# LB_BIT_o21_number-v03_rev5_4.net
KiCad netlist of a schematic drawn in EAGLE
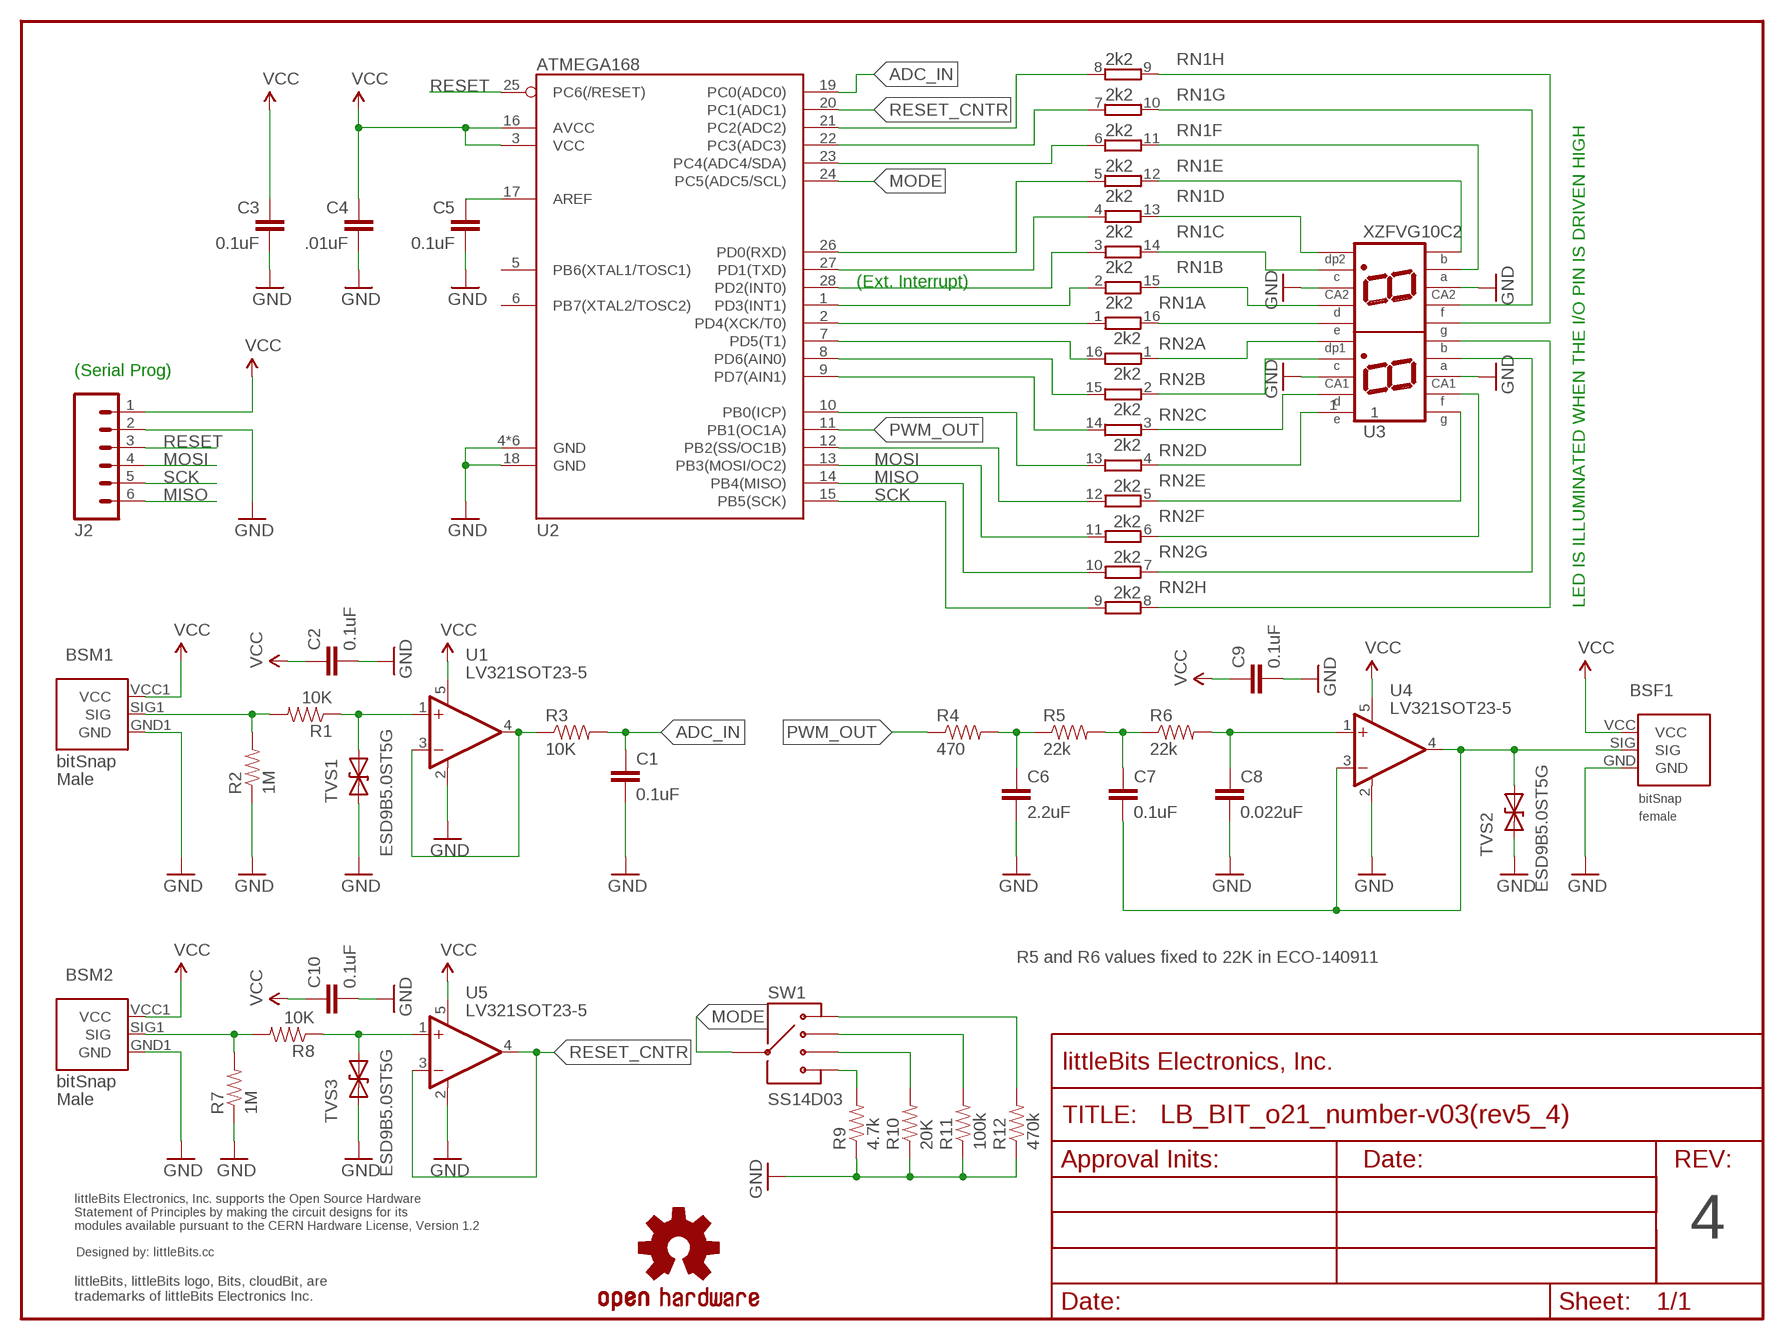
[diagram p0: schematic, sheet 1]

(export (version "E")
  (design (tool "Eeschema 10.0.6"))
  (components
    (comp (ref "BSF1")
      (value "BITSNAP_V03_FEMALE")
      (footprint "eagle-import:BITSNAP_V03_FEMALE")
      (libsource (lib "eagle-import") (part "BITSNAP_V03_FEMALE"))
    )
    (comp (ref "BSM1")
      (value "BITSNAP_V03_MALE")
      (footprint "eagle-import:BITSNAP_V03_MALE")
      (libsource (lib "eagle-import") (part "BITSNAP_V03_MALE"))
    )
    (comp (ref "BSM2")
      (value "BITSNAP_V03_MALE")
      (footprint "eagle-import:BITSNAP_V03_MALE")
      (libsource (lib "eagle-import") (part "BITSNAP_V03_MALE"))
    )
    (comp (ref "C1")
      (value "0.1uF")
      (footprint "eagle-import:CAP-0603")
      (libsource (lib "eagle-import") (part "CAPCAP-0603"))
    )
    (comp (ref "C2")
      (value "0.1uF")
      (footprint "eagle-import:CAP-0603")
      (libsource (lib "eagle-import") (part "CAPCAP-0603"))
    )
    (comp (ref "C3")
      (value "0.1uF")
      (footprint "eagle-import:CAP-0603")
      (libsource (lib "eagle-import") (part "CAPCAP-0603"))
    )
    (comp (ref "C4")
      (value ".01uF")
      (footprint "eagle-import:CAP-0603")
      (libsource (lib "eagle-import") (part "CAPCAP-0603"))
    )
    (comp (ref "C5")
      (value "0.1uF")
      (footprint "eagle-import:CAP-0603")
      (libsource (lib "eagle-import") (part "CAPCAP-0603"))
    )
    (comp (ref "C6")
      (value "2.2uF")
      (footprint "eagle-import:CAP-0603")
      (libsource (lib "eagle-import") (part "CAPCAP-0603"))
    )
    (comp (ref "C7")
      (value "0.1uF")
      (footprint "eagle-import:CAP-0603")
      (libsource (lib "eagle-import") (part "CAPCAP-0603"))
    )
    (comp (ref "C8")
      (value "0.022uF")
      (footprint "eagle-import:CAP-0603")
      (libsource (lib "eagle-import") (part "CAPCAP-0603"))
    )
    (comp (ref "C9")
      (value "0.1uF")
      (footprint "eagle-import:CAP-0603")
      (libsource (lib "eagle-import") (part "CAPCAP-0603"))
    )
    (comp (ref "C10")
      (value "0.1uF")
      (footprint "eagle-import:CAP-0603")
      (libsource (lib "eagle-import") (part "CAPCAP-0603"))
    )
    (comp (ref "J2")
      (value "HRD-60.1INCH_NO_SILKSCREEN")
      (footprint "eagle-import:SIP6-SM-0.1IN-NOS.S.")
      (libsource (lib "eagle-import") (part "HRD-60.1INCH_NO_SILKSCREEN"))
    )
    (comp (ref "R1")
      (value "10K")
      (footprint "eagle-import:RES-0603")
      (libsource (lib "eagle-import") (part "RESISTOR0603"))
    )
    (comp (ref "R2")
      (value "1M")
      (footprint "eagle-import:RES-0603")
      (libsource (lib "eagle-import") (part "RESISTOR0603"))
    )
    (comp (ref "R3")
      (value "10K")
      (footprint "eagle-import:RES-0603")
      (libsource (lib "eagle-import") (part "RESISTOR0603"))
    )
    (comp (ref "R4")
      (value "470")
      (footprint "eagle-import:RES-0603")
      (libsource (lib "eagle-import") (part "RESISTOR0603"))
    )
    (comp (ref "R5")
      (value "22k")
      (footprint "eagle-import:RES-0603")
      (libsource (lib "eagle-import") (part "RESISTOR0603"))
    )
    (comp (ref "R6")
      (value "22k")
      (footprint "eagle-import:RES-0603")
      (libsource (lib "eagle-import") (part "RESISTOR0603"))
    )
    (comp (ref "R7")
      (value "1M")
      (footprint "eagle-import:RES-0603")
      (libsource (lib "eagle-import") (part "RESISTOR0603"))
    )
    (comp (ref "R8")
      (value "10K")
      (footprint "eagle-import:RES-0603")
      (libsource (lib "eagle-import") (part "RESISTOR0603"))
    )
    (comp (ref "R9")
      (value "4.7k")
      (footprint "eagle-import:RES-0603")
      (libsource (lib "eagle-import") (part "RESISTOR0603"))
    )
    (comp (ref "R10")
      (value "20K")
      (footprint "eagle-import:RES-0603")
      (libsource (lib "eagle-import") (part "RESISTOR0603"))
    )
    (comp (ref "R11")
      (value "100k")
      (footprint "eagle-import:RES-0603")
      (libsource (lib "eagle-import") (part "RESISTOR0603"))
    )
    (comp (ref "R12")
      (value "470k")
      (footprint "eagle-import:RES-0603")
      (libsource (lib "eagle-import") (part "RESISTOR0603"))
    )
    (comp (ref "RN1")
      (value "2k2")
      (footprint "eagle-import:EXB2HV")
      (libsource (lib "eagle-import") (part "RES_ARRAY8_DIPEXB2HV"))
    )
    (comp (ref "RN2")
      (value "2k2")
      (footprint "eagle-import:EXB2HV")
      (libsource (lib "eagle-import") (part "RES_ARRAY8_DIPEXB2HV"))
    )
    (comp (ref "SW1")
      (value "SS14D03")
      (footprint "eagle-import:SWITCH-SLIDE-SP4T-SS14D03")
      (fields (field (name "MFG") "Vimex") (field (name "MPN") "SS-14D03"))
      (libsource (lib "eagle-import") (part "SWITCH-SLIDE-SS14D03"))
    )
    (comp (ref "TVS1")
      (value "ESD9B5.0ST5G")
      (footprint "eagle-import:SOD-923")
      (libsource (lib "eagle-import") (part "DIODE-TVSSOD-923"))
    )
    (comp (ref "TVS2")
      (value "ESD9B5.0ST5G")
      (footprint "eagle-import:SOD-923")
      (libsource (lib "eagle-import") (part "DIODE-TVSSOD-923"))
    )
    (comp (ref "TVS3")
      (value "ESD9B5.0ST5G")
      (footprint "eagle-import:SOD-923")
      (libsource (lib "eagle-import") (part "DIODE-TVSSOD-923"))
    )
    (comp (ref "U$1")
      (value "FRAME-LETTER-OHWOHW")
      (footprint "eagle-import:FABDWG01-OHW")
      (libsource (lib "eagle-import") (part "FRAME-LETTER-OHWOHW"))
    )
    (comp (ref "U$2")
      (value "OSHWCREDIT")
      (footprint "eagle-import:OSHWCREDIT")
      (libsource (lib "eagle-import") (part "OSHWCREDIT"))
    )
    (comp (ref "U$27")
      (value "OSHW-LOGOL")
      (footprint "eagle-import:OSHW-LOGO-L")
      (libsource (lib "eagle-import") (part "OSHW-LOGOL"))
    )
    (comp (ref "U1")
      (value "LV321SOT23-5")
      (footprint "eagle-import:SOT23-5")
      (libsource (lib "eagle-import") (part "LV321SOT23-5"))
    )
    (comp (ref "U2")
      (value "ATMEGA168")
      (footprint "eagle-import:VQFN28")
      (libsource (lib "eagle-import") (part "ATMEGA168-28PINVFQFN-28"))
    )
    (comp (ref "U3")
      (value "XZFVG10C2")
      (footprint "eagle-import:LED-DUAL7SEG-SM")
      (libsource (lib "eagle-import") (part "LED-DUAL7SEG10.16MMDIGITS"))
    )
    (comp (ref "U4")
      (value "LV321SOT23-5")
      (footprint "eagle-import:SOT23-5")
      (libsource (lib "eagle-import") (part "LV321SOT23-5"))
    )
    (comp (ref "U5")
      (value "LV321SOT23-5")
      (footprint "eagle-import:SOT23-5")
      (libsource (lib "eagle-import") (part "LV321SOT23-5"))
    )
  )
  (nets
    (net (code "1") (name "/MISO") (class "Default")
      (node (ref "J2") (pin "6") (pinfunction "6_6") (pintype "passive"))
      (node (ref "RN2") (pin "10") (pinfunction "2_10") (pintype "passive"))
      (node (ref "U2") (pin "14") (pinfunction "PB4(MISO)_14") (pintype "bidirectional"))
    )
    (net (code "2") (name "/MOSI") (class "Default")
      (node (ref "J2") (pin "4") (pinfunction "4_4") (pintype "passive"))
      (node (ref "RN2") (pin "11") (pinfunction "2_11") (pintype "passive"))
      (node (ref "U2") (pin "13") (pinfunction "PB3(MOSI/OC2)_13") (pintype "bidirectional"))
    )
    (net (code "3") (name "/RESET") (class "Default")
      (node (ref "J2") (pin "3") (pinfunction "3_3") (pintype "passive"))
      (node (ref "U2") (pin "25") (pinfunction "PC6(/RESET)_25") (pintype "bidirectional"))
    )
    (net (code "4") (name "/SCK") (class "Default")
      (node (ref "J2") (pin "5") (pinfunction "5_5") (pintype "passive"))
      (node (ref "RN2") (pin "9") (pinfunction "2_9") (pintype "passive"))
      (node (ref "U2") (pin "15") (pinfunction "PB5(SCK)_15") (pintype "bidirectional"))
    )
    (net (code "5") (name "ADC_IN") (class "Default")
      (node (ref "C1") (pin "1") (pinfunction "1_1") (pintype "passive"))
      (node (ref "R3") (pin "2") (pinfunction "2_2") (pintype "passive"))
      (node (ref "U2") (pin "19") (pinfunction "PC0(ADC0)_19") (pintype "bidirectional"))
    )
    (net (code "6") (name "GND") (class "Default")
      (node (ref "BSF1") (pin "GND") (pinfunction "GND_GND") (pintype "bidirectional"))
      (node (ref "BSM1") (pin "GND1") (pinfunction "GND_GND1") (pintype "bidirectional"))
      (node (ref "BSM2") (pin "GND1") (pinfunction "GND_GND1") (pintype "bidirectional"))
      (node (ref "C1") (pin "2") (pinfunction "2_2") (pintype "passive"))
      (node (ref "C10") (pin "2") (pinfunction "2_2") (pintype "passive"))
      (node (ref "C2") (pin "2") (pinfunction "2_2") (pintype "passive"))
      (node (ref "C3") (pin "2") (pinfunction "2_2") (pintype "passive"))
      (node (ref "C4") (pin "2") (pinfunction "2_2") (pintype "passive"))
      (node (ref "C5") (pin "2") (pinfunction "2_2") (pintype "passive"))
      (node (ref "C6") (pin "2") (pinfunction "2_2") (pintype "passive"))
      (node (ref "C8") (pin "2") (pinfunction "2_2") (pintype "passive"))
      (node (ref "C9") (pin "2") (pinfunction "2_2") (pintype "passive"))
      (node (ref "J2") (pin "2") (pinfunction "2_2") (pintype "passive"))
      (node (ref "R10") (pin "1") (pinfunction "1_1") (pintype "passive"))
      (node (ref "R11") (pin "1") (pinfunction "1_1") (pintype "passive"))
      (node (ref "R12") (pin "1") (pinfunction "1_1") (pintype "passive"))
      (node (ref "R2") (pin "1") (pinfunction "1_1") (pintype "passive"))
      (node (ref "R7") (pin "1") (pinfunction "1_1") (pintype "passive"))
      (node (ref "R9") (pin "1") (pinfunction "1_1") (pintype "passive"))
      (node (ref "TVS1") (pin "1") (pinfunction "A_1") (pintype "passive"))
      (node (ref "TVS2") (pin "1") (pinfunction "A_1") (pintype "passive"))
      (node (ref "TVS3") (pin "1") (pinfunction "A_1") (pintype "passive"))
      (node (ref "U1") (pin "2") (pinfunction "V-_2") (pintype "power_in"))
      (node (ref "U2") (pin "18") (pinfunction "GND_18") (pintype "bidirectional"))
      (node (ref "U2") (pin "4") (pinfunction "GND_4") (pintype "bidirectional"))
      (node (ref "U2") (pin "TH") (pinfunction "GND_TH") (pintype "bidirectional"))
      (node (ref "U2") (pin "TH@1") (pinfunction "GND_TH@1") (pintype "bidirectional"))
      (node (ref "U2") (pin "TH@2") (pinfunction "GND_TH@2") (pintype "bidirectional"))
      (node (ref "U2") (pin "TH@3") (pinfunction "GND_TH@3") (pintype "bidirectional"))
      (node (ref "U2") (pin "TH@4") (pinfunction "GND_TH@4") (pintype "bidirectional"))
      (node (ref "U3") (pin "13") (pinfunction "13_13") (pintype "passive"))
      (node (ref "U3") (pin "18") (pinfunction "18_18") (pintype "passive"))
      (node (ref "U3") (pin "3") (pinfunction "3_3") (pintype "passive"))
      (node (ref "U3") (pin "8") (pinfunction "8_8") (pintype "passive"))
      (node (ref "U4") (pin "2") (pinfunction "V-_2") (pintype "power_in"))
      (node (ref "U5") (pin "2") (pinfunction "V-_2") (pintype "power_in"))
    )
    (net (code "7") (name "MODE") (class "Default")
      (node (ref "SW1") (pin "COM") (pinfunction "COM_COM") (pintype "bidirectional"))
      (node (ref "U2") (pin "24") (pinfunction "PC5(ADC5/SCL)_24") (pintype "bidirectional"))
    )
    (net (code "8") (name "Net-(BSM1-SIG)") (class "Default")
      (node (ref "BSM1") (pin "SIG1") (pinfunction "SIG_SIG1") (pintype "bidirectional"))
      (node (ref "R1") (pin "2") (pinfunction "2_2") (pintype "passive"))
      (node (ref "R2") (pin "2") (pinfunction "2_2") (pintype "passive"))
    )
    (net (code "9") (name "Net-(BSM2-SIG)") (class "Default")
      (node (ref "BSM2") (pin "SIG1") (pinfunction "SIG_SIG1") (pintype "bidirectional"))
      (node (ref "R7") (pin "2") (pinfunction "2_2") (pintype "passive"))
      (node (ref "R8") (pin "2") (pinfunction "2_2") (pintype "passive"))
    )
    (net (code "10") (name "Net-(C6-Pad1)") (class "Default")
      (node (ref "C6") (pin "1") (pinfunction "1_1") (pintype "passive"))
      (node (ref "R4") (pin "2") (pinfunction "2_2") (pintype "passive"))
      (node (ref "R5") (pin "1") (pinfunction "1_1") (pintype "passive"))
    )
    (net (code "11") (name "Net-(C7-Pad1)") (class "Default")
      (node (ref "C7") (pin "1") (pinfunction "1_1") (pintype "passive"))
      (node (ref "R5") (pin "2") (pinfunction "2_2") (pintype "passive"))
      (node (ref "R6") (pin "1") (pinfunction "1_1") (pintype "passive"))
    )
    (net (code "12") (name "Net-(R9-Pad2)") (class "Default")
      (node (ref "R9") (pin "2") (pinfunction "2_2") (pintype "passive"))
      (node (ref "SW1") (pin "4") (pinfunction "4_4") (pintype "bidirectional"))
    )
    (net (code "13") (name "Net-(R10-Pad2)") (class "Default")
      (node (ref "R10") (pin "2") (pinfunction "2_2") (pintype "passive"))
      (node (ref "SW1") (pin "3") (pinfunction "3_3") (pintype "bidirectional"))
    )
    (net (code "14") (name "Net-(R11-Pad2)") (class "Default")
      (node (ref "R11") (pin "2") (pinfunction "2_2") (pintype "passive"))
      (node (ref "SW1") (pin "2") (pinfunction "2_2") (pintype "bidirectional"))
    )
    (net (code "15") (name "Net-(R12-Pad2)") (class "Default")
      (node (ref "R12") (pin "2") (pinfunction "2_2") (pintype "passive"))
      (node (ref "SW1") (pin "1") (pinfunction "1_1") (pintype "bidirectional"))
    )
    (net (code "16") (name "Net-(RN1A-2)") (class "Default")
      (node (ref "RN1") (pin "16") (pinfunction "2_16") (pintype "passive"))
      (node (ref "U3") (pin "6") (pinfunction "6_6") (pintype "passive"))
    )
    (net (code "17") (name "Net-(RN1B-1)") (class "Default")
      (node (ref "RN1") (pin "2") (pinfunction "1_2") (pintype "passive"))
      (node (ref "U2") (pin "1") (pinfunction "PD3(INT1)_1") (pintype "bidirectional"))
    )
    (net (code "18") (name "Net-(RN1B-2)") (class "Default")
      (node (ref "RN1") (pin "15") (pinfunction "2_15") (pintype "passive"))
      (node (ref "U3") (pin "7") (pinfunction "7_7") (pintype "passive"))
    )
    (net (code "19") (name "Net-(RN1C-1)") (class "Default")
      (node (ref "RN1") (pin "3") (pinfunction "1_3") (pintype "passive"))
      (node (ref "U2") (pin "28") (pinfunction "PD2(INT0)_28") (pintype "bidirectional"))
    )
    (net (code "20") (name "Net-(RN1C-2)") (class "Default")
      (node (ref "RN1") (pin "14") (pinfunction "2_14") (pintype "passive"))
      (node (ref "U3") (pin "9") (pinfunction "9_9") (pintype "passive"))
    )
    (net (code "21") (name "Net-(RN1D-1)") (class "Default")
      (node (ref "RN1") (pin "4") (pinfunction "1_4") (pintype "passive"))
      (node (ref "U2") (pin "27") (pinfunction "PD1(TXD)_27") (pintype "bidirectional"))
    )
    (net (code "22") (name "Net-(RN1D-2)") (class "Default")
      (node (ref "RN1") (pin "13") (pinfunction "2_13") (pintype "passive"))
      (node (ref "U3") (pin "10") (pinfunction "10_10") (pintype "passive"))
    )
    (net (code "23") (name "Net-(RN1E-1)") (class "Default")
      (node (ref "RN1") (pin "5") (pinfunction "1_5") (pintype "passive"))
      (node (ref "U2") (pin "26") (pinfunction "PD0(RXD)_26") (pintype "bidirectional"))
    )
    (net (code "24") (name "Net-(RN1E-2)") (class "Default")
      (node (ref "RN1") (pin "12") (pinfunction "2_12") (pintype "passive"))
      (node (ref "U3") (pin "11") (pinfunction "11_11") (pintype "passive"))
    )
    (net (code "25") (name "Net-(RN1F-1)") (class "Default")
      (node (ref "RN1") (pin "6") (pinfunction "1_6") (pintype "passive"))
      (node (ref "U2") (pin "23") (pinfunction "PC4(ADC4/SDA)_23") (pintype "bidirectional"))
    )
    (net (code "26") (name "Net-(RN1F-2)") (class "Default")
      (node (ref "RN1") (pin "11") (pinfunction "2_11") (pintype "passive"))
      (node (ref "U3") (pin "12") (pinfunction "12_12") (pintype "passive"))
    )
    (net (code "27") (name "Net-(RN1G-1)") (class "Default")
      (node (ref "RN1") (pin "7") (pinfunction "1_7") (pintype "passive"))
      (node (ref "U2") (pin "22") (pinfunction "PC3(ADC3)_22") (pintype "bidirectional"))
    )
    (net (code "28") (name "Net-(RN1G-2)") (class "Default")
      (node (ref "RN1") (pin "10") (pinfunction "2_10") (pintype "passive"))
      (node (ref "U3") (pin "14") (pinfunction "14_14") (pintype "passive"))
    )
    (net (code "29") (name "Net-(RN1H-1)") (class "Default")
      (node (ref "RN1") (pin "8") (pinfunction "1_8") (pintype "passive"))
      (node (ref "U2") (pin "21") (pinfunction "PC2(ADC2)_21") (pintype "bidirectional"))
    )
    (net (code "30") (name "Net-(RN1H-2)") (class "Default")
      (node (ref "RN1") (pin "9") (pinfunction "2_9") (pintype "passive"))
      (node (ref "U3") (pin "15") (pinfunction "15_15") (pintype "passive"))
    )
    (net (code "31") (name "Net-(RN2-Pad1)") (class "Default")
      (node (ref "RN2") (pin "1") (pinfunction "1_1") (pintype "passive"))
      (node (ref "U3") (pin "5") (pinfunction "5_5") (pintype "passive"))
    )
    (net (code "32") (name "Net-(RN2A-2)") (class "Default")
      (node (ref "RN2") (pin "16") (pinfunction "2_16") (pintype "passive"))
      (node (ref "U2") (pin "7") (pinfunction "PD5(T1)_7") (pintype "bidirectional"))
    )
    (net (code "33") (name "Net-(RN2B-1)") (class "Default")
      (node (ref "RN2") (pin "2") (pinfunction "1_2") (pintype "passive"))
      (node (ref "U3") (pin "4") (pinfunction "4_4") (pintype "passive"))
    )
    (net (code "34") (name "Net-(RN2B-2)") (class "Default")
      (node (ref "RN2") (pin "15") (pinfunction "2_15") (pintype "passive"))
      (node (ref "U2") (pin "8") (pinfunction "PD6(AIN0)_8") (pintype "bidirectional"))
    )
    (net (code "35") (name "Net-(RN2C-1)") (class "Default")
      (node (ref "RN2") (pin "3") (pinfunction "1_3") (pintype "passive"))
      (node (ref "U3") (pin "2") (pinfunction "2_2") (pintype "passive"))
    )
    (net (code "36") (name "Net-(RN2C-2)") (class "Default")
      (node (ref "RN2") (pin "14") (pinfunction "2_14") (pintype "passive"))
      (node (ref "U2") (pin "9") (pinfunction "PD7(AIN1)_9") (pintype "bidirectional"))
    )
    (net (code "37") (name "Net-(RN2D-1)") (class "Default")
      (node (ref "RN2") (pin "4") (pinfunction "1_4") (pintype "passive"))
      (node (ref "U3") (pin "1") (pinfunction "1_1") (pintype "passive"))
    )
    (net (code "38") (name "Net-(RN2D-2)") (class "Default")
      (node (ref "RN2") (pin "13") (pinfunction "2_13") (pintype "passive"))
      (node (ref "U2") (pin "10") (pinfunction "PB0(ICP)_10") (pintype "bidirectional"))
    )
    (net (code "39") (name "Net-(RN2E-1)") (class "Default")
      (node (ref "RN2") (pin "5") (pinfunction "1_5") (pintype "passive"))
      (node (ref "U3") (pin "20") (pinfunction "20_20") (pintype "passive"))
    )
    (net (code "40") (name "Net-(RN2E-2)") (class "Default")
      (node (ref "RN2") (pin "12") (pinfunction "2_12") (pintype "passive"))
      (node (ref "U2") (pin "12") (pinfunction "PB2(SS/OC1B)_12") (pintype "bidirectional"))
    )
    (net (code "41") (name "Net-(RN2F-1)") (class "Default")
      (node (ref "RN2") (pin "6") (pinfunction "1_6") (pintype "passive"))
      (node (ref "U3") (pin "19") (pinfunction "19_19") (pintype "passive"))
    )
    (net (code "42") (name "Net-(RN2G-1)") (class "Default")
      (node (ref "RN2") (pin "7") (pinfunction "1_7") (pintype "passive"))
      (node (ref "U3") (pin "17") (pinfunction "17_17") (pintype "passive"))
    )
    (net (code "43") (name "Net-(RN2H-1)") (class "Default")
      (node (ref "RN2") (pin "8") (pinfunction "1_8") (pintype "passive"))
      (node (ref "U3") (pin "16") (pinfunction "16_16") (pintype "passive"))
    )
    (net (code "44") (name "Net-(TVS1-C)") (class "Default")
      (node (ref "R1") (pin "1") (pinfunction "1_1") (pintype "passive"))
      (node (ref "TVS1") (pin "2") (pinfunction "C_2") (pintype "passive"))
      (node (ref "U1") (pin "1") (pinfunction "+IN_1") (pintype "input"))
    )
    (net (code "45") (name "Net-(TVS2-C)") (class "Default")
      (node (ref "BSF1") (pin "SIG") (pinfunction "SIG_SIG") (pintype "bidirectional"))
      (node (ref "C7") (pin "2") (pinfunction "2_2") (pintype "passive"))
      (node (ref "TVS2") (pin "2") (pinfunction "C_2") (pintype "passive"))
      (node (ref "U4") (pin "3") (pinfunction "-IN_3") (pintype "input"))
      (node (ref "U4") (pin "4") (pinfunction "OUT_4") (pintype "output"))
    )
    (net (code "46") (name "Net-(TVS3-C)") (class "Default")
      (node (ref "R8") (pin "1") (pinfunction "1_1") (pintype "passive"))
      (node (ref "TVS3") (pin "2") (pinfunction "C_2") (pintype "passive"))
      (node (ref "U5") (pin "1") (pinfunction "+IN_1") (pintype "input"))
    )
    (net (code "47") (name "Net-(U1--IN)") (class "Default")
      (node (ref "R3") (pin "1") (pinfunction "1_1") (pintype "passive"))
      (node (ref "U1") (pin "3") (pinfunction "-IN_3") (pintype "input"))
      (node (ref "U1") (pin "4") (pinfunction "OUT_4") (pintype "output"))
    )
    (net (code "48") (name "Net-(U2-AREF)") (class "Default")
      (node (ref "C5") (pin "1") (pinfunction "1_1") (pintype "passive"))
      (node (ref "U2") (pin "17") (pinfunction "AREF_17") (pintype "bidirectional"))
    )
    (net (code "49") (name "Net-(U2-PD4(XCK{slash}T0))") (class "Default")
      (node (ref "RN1") (pin "1") (pinfunction "1_1") (pintype "passive"))
      (node (ref "U2") (pin "2") (pinfunction "PD4(XCK/T0)_2") (pintype "bidirectional"))
    )
    (net (code "50") (name "Net-(U4-+IN)") (class "Default")
      (node (ref "C8") (pin "1") (pinfunction "1_1") (pintype "passive"))
      (node (ref "R6") (pin "2") (pinfunction "2_2") (pintype "passive"))
      (node (ref "U4") (pin "1") (pinfunction "+IN_1") (pintype "input"))
    )
    (net (code "51") (name "PWM_OUT") (class "Default")
      (node (ref "R4") (pin "1") (pinfunction "1_1") (pintype "passive"))
      (node (ref "U2") (pin "11") (pinfunction "PB1(OC1A)_11") (pintype "bidirectional"))
    )
    (net (code "52") (name "RESET_CNTR") (class "Default")
      (node (ref "U2") (pin "20") (pinfunction "PC1(ADC1)_20") (pintype "bidirectional"))
      (node (ref "U5") (pin "3") (pinfunction "-IN_3") (pintype "input"))
      (node (ref "U5") (pin "4") (pinfunction "OUT_4") (pintype "output"))
    )
    (net (code "53") (name "VCC") (class "Default")
      (node (ref "BSF1") (pin "VCC") (pinfunction "VCC_VCC") (pintype "bidirectional"))
      (node (ref "BSM1") (pin "VCC1") (pinfunction "VCC_VCC1") (pintype "bidirectional"))
      (node (ref "BSM2") (pin "VCC1") (pinfunction "VCC_VCC1") (pintype "bidirectional"))
      (node (ref "C10") (pin "1") (pinfunction "1_1") (pintype "passive"))
      (node (ref "C2") (pin "1") (pinfunction "1_1") (pintype "passive"))
      (node (ref "C3") (pin "1") (pinfunction "1_1") (pintype "passive"))
      (node (ref "C4") (pin "1") (pinfunction "1_1") (pintype "passive"))
      (node (ref "C9") (pin "1") (pinfunction "1_1") (pintype "passive"))
      (node (ref "J2") (pin "1") (pinfunction "1_1") (pintype "passive"))
      (node (ref "U1") (pin "5") (pinfunction "V+_5") (pintype "power_in"))
      (node (ref "U2") (pin "16") (pinfunction "AVCC_16") (pintype "bidirectional"))
      (node (ref "U2") (pin "3") (pinfunction "VCC_3") (pintype "bidirectional"))
      (node (ref "U4") (pin "5") (pinfunction "V+_5") (pintype "power_in"))
      (node (ref "U5") (pin "5") (pinfunction "V+_5") (pintype "power_in"))
    )
    (net (code "54") (name "unconnected-(U2-PB6(XTAL1{slash}TOSC1)-Pad5)") (class "Default")
      (node (ref "U2") (pin "5") (pinfunction "PB6(XTAL1/TOSC1)_5") (pintype "bidirectional"))
    )
    (net (code "55") (name "unconnected-(U2-PB7(XTAL2{slash}TOSC2)-Pad6)") (class "Default")
      (node (ref "U2") (pin "6") (pinfunction "PB7(XTAL2/TOSC2)_6") (pintype "bidirectional"))
    )
  )
)
